# controller.net
KiCad netlist of a schematic drawn in EAGLE
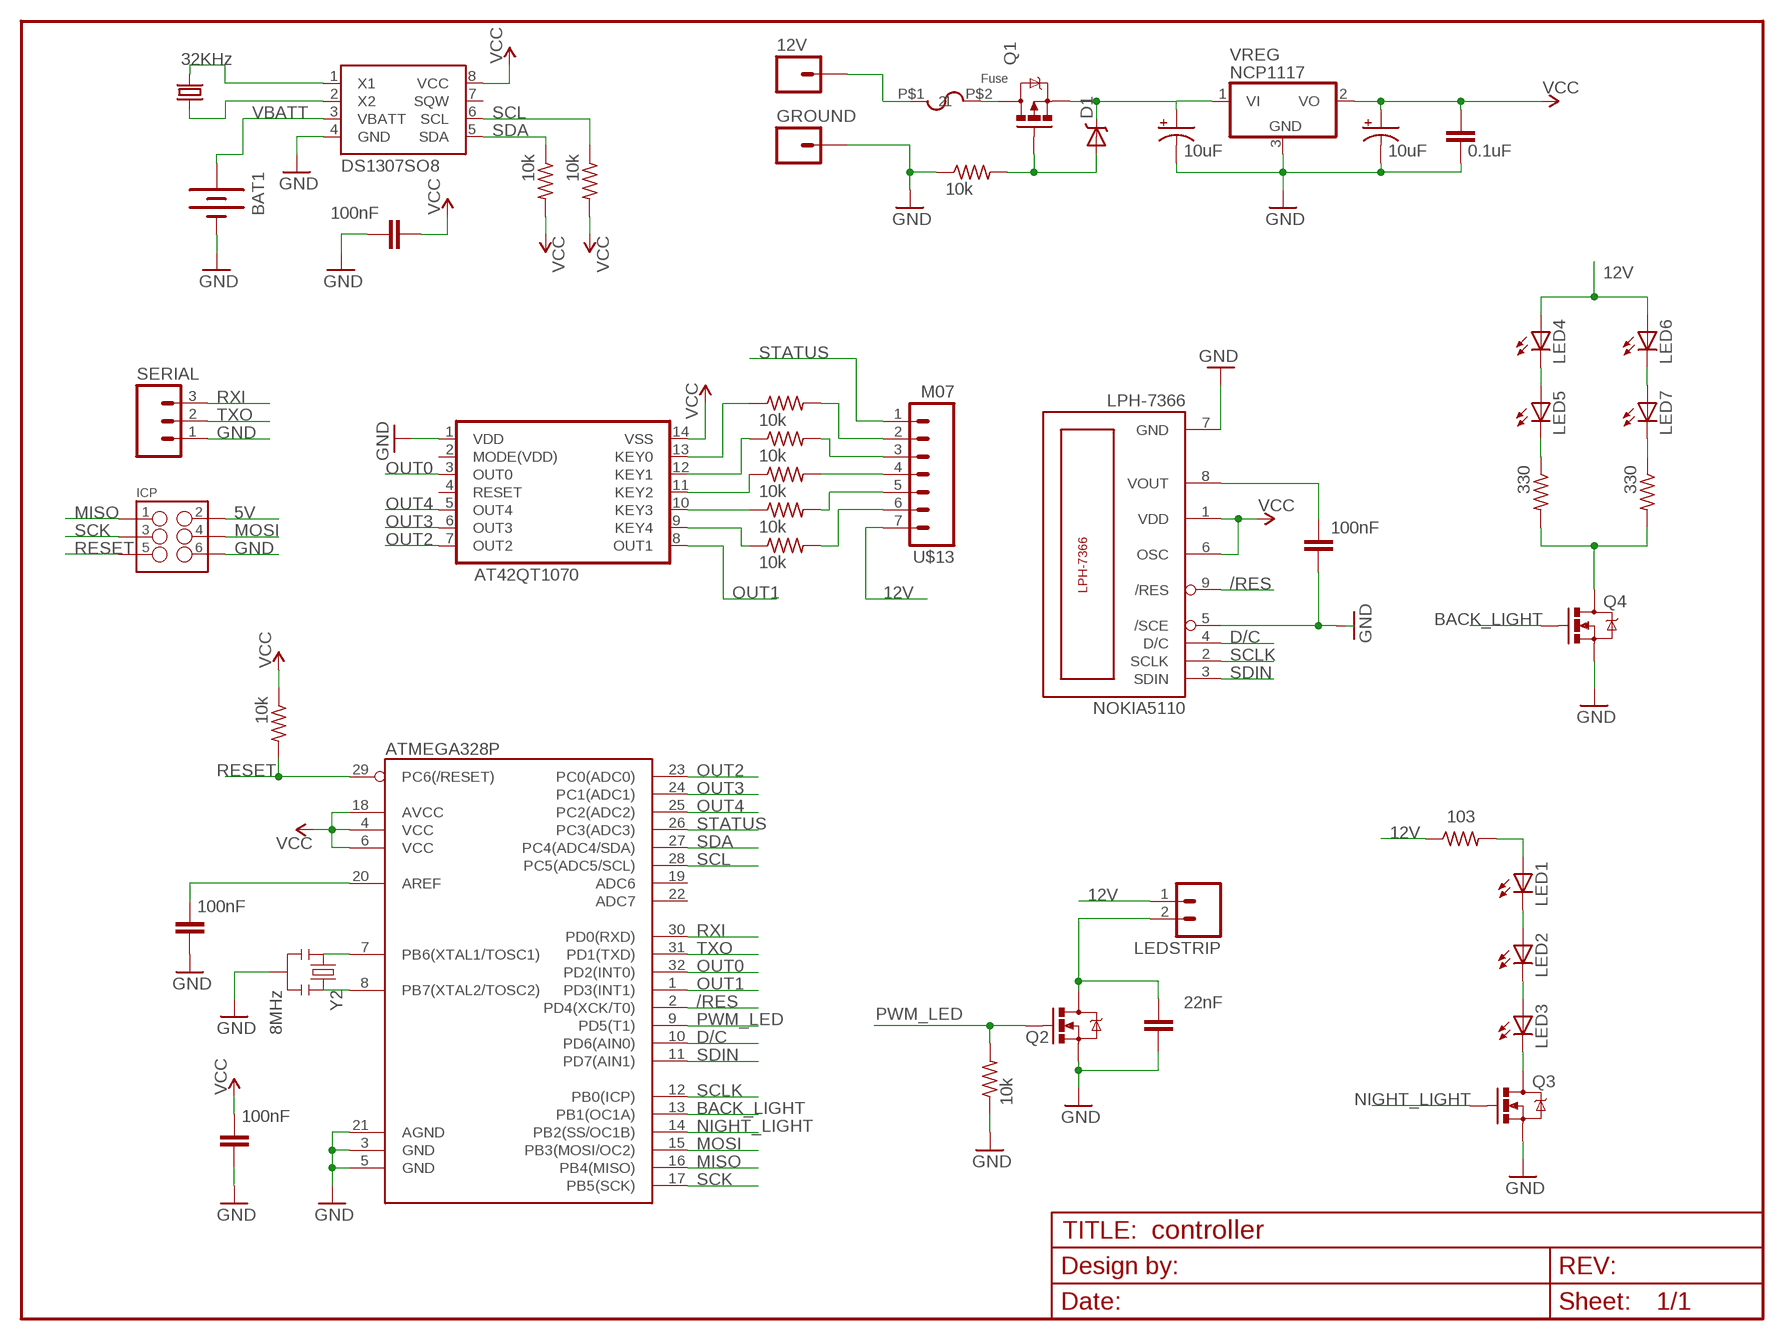
[diagram p0: schematic, sheet 1]

(export (version "E")
  (design (tool "Eeschema 10.0.6"))
  (components
    (comp (ref "12V")
      (value "M01PTH_LONGPAD")
      (footprint "eagle-import:1X01_LONGPAD")
      (libsource (lib "eagle-import") (part "M01PTH_LONGPAD"))
    )
    (comp (ref "AT42QT1070")
      (value "AT42QT1070")
      (footprint "eagle-import:SOIC-14")
      (libsource (lib "eagle-import") (part "AT42QT1070"))
    )
    (comp (ref "BAT1")
      (value "BATTERY12MM")
      (footprint "eagle-import:BATTCON_12MM")
      (libsource (lib "eagle-import") (part "BATTERY12MM"))
    )
    (comp (ref "C1")
      (value "100nF")
      (footprint "eagle-import:0805")
      (libsource (lib "eagle-import") (part "CAP0805"))
    )
    (comp (ref "C2")
      (value "100nF")
      (footprint "eagle-import:0805")
      (libsource (lib "eagle-import") (part "CAP0805"))
    )
    (comp (ref "C3")
      (value "100nF")
      (footprint "eagle-import:0805")
      (libsource (lib "eagle-import") (part "CAP0805"))
    )
    (comp (ref "C4")
      (value "22nF")
      (footprint "eagle-import:0805")
      (libsource (lib "eagle-import") (part "CAP0805"))
    )
    (comp (ref "C5")
      (value "10uF")
      (footprint "eagle-import:EIA3216-KIT")
      (libsource (lib "eagle-import") (part "CAP_POL1206-KIT"))
    )
    (comp (ref "C6")
      (value "100nF")
      (footprint "eagle-import:0805")
      (libsource (lib "eagle-import") (part "CAP0805"))
    )
    (comp (ref "C7")
      (value "10uF")
      (footprint "eagle-import:EIA3216-KIT")
      (libsource (lib "eagle-import") (part "CAP_POL1206-KIT"))
    )
    (comp (ref "C8")
      (value "0.1uF")
      (footprint "eagle-import:0805")
      (libsource (lib "eagle-import") (part "CAP0805"))
    )
    (comp (ref "D1")
      (value "DIODE-SCHOTTKYDO-214AA")
      (footprint "eagle-import:DO-214AA")
      (libsource (lib "eagle-import") (part "DIODE-SCHOTTKYDO-214AA"))
    )
    (comp (ref "GROUND")
      (value "M01PTH_LONGPAD")
      (footprint "eagle-import:1X01_LONGPAD")
      (libsource (lib "eagle-import") (part "M01PTH_LONGPAD"))
    )
    (comp (ref "ICP")
      (value "M03X2POGO_PINS")
      (footprint "eagle-import:2X3_POGO")
      (libsource (lib "eagle-import") (part "M03X2POGO_PINS"))
    )
    (comp (ref "LED1")
      (value "LED")
      (footprint "eagle-import:SIDEVIEW-LED")
      (libsource (lib "eagle-import") (part "LED"))
    )
    (comp (ref "LED2")
      (value "LED")
      (footprint "eagle-import:SIDEVIEW-LED")
      (libsource (lib "eagle-import") (part "LED"))
    )
    (comp (ref "LED3")
      (value "LED")
      (footprint "eagle-import:SIDEVIEW-LED")
      (libsource (lib "eagle-import") (part "LED"))
    )
    (comp (ref "LED4")
      (value "LED0603")
      (footprint "eagle-import:LED-0603")
      (libsource (lib "eagle-import") (part "LED0603"))
    )
    (comp (ref "LED5")
      (value "LED0603")
      (footprint "eagle-import:LED-0603")
      (libsource (lib "eagle-import") (part "LED0603"))
    )
    (comp (ref "LED6")
      (value "LED0603")
      (footprint "eagle-import:LED-0603")
      (libsource (lib "eagle-import") (part "LED0603"))
    )
    (comp (ref "LED7")
      (value "LED0603")
      (footprint "eagle-import:LED-0603")
      (libsource (lib "eagle-import") (part "LED0603"))
    )
    (comp (ref "LEDSTRIP")
      (value "M02LOCK_LONGPADS")
      (footprint "eagle-import:1X02_LOCK_LONGPADS")
      (libsource (lib "eagle-import") (part "M02LOCK_LONGPADS"))
    )
    (comp (ref "NOKIA5110")
      (value "LPH-7366")
      (footprint "eagle-import:NOKIA5110")
      (libsource (lib "eagle-import") (part "LPH-7366"))
    )
    (comp (ref "Q1")
      (value "MOSFET_PCHANNEL")
      (footprint "eagle-import:DPAK")
      (libsource (lib "eagle-import") (part "MOSFET_PCHANNEL"))
    )
    (comp (ref "Q2")
      (value "MOSFET-NCHANNELFDD8780")
      (footprint "eagle-import:DPAK@1")
      (libsource (lib "eagle-import") (part "MOSFET-NCHANNELFDD8780"))
    )
    (comp (ref "Q3")
      (value "MOSFET-NCHANNELBSS123LT1G")
      (footprint "eagle-import:SOT23")
      (libsource (lib "eagle-import") (part "MOSFET-NCHANNELBSS123LT1G"))
    )
    (comp (ref "Q4")
      (value "MOSFET-NCHANNELBSS123LT1G")
      (footprint "eagle-import:SOT23")
      (libsource (lib "eagle-import") (part "MOSFET-NCHANNELBSS123LT1G"))
    )
    (comp (ref "SERIAL")
      (value "M03POGO_PIN_HOLES_ONLY")
      (footprint "eagle-import:1X03_PP_HOLES_ONLY")
      (libsource (lib "eagle-import") (part "M03POGO_PIN_HOLES_ONLY"))
    )
    (comp (ref "U$1")
      (value "FRAME_LETTER")
      (footprint "eagle-import:CREATIVE_COMMONS")
      (libsource (lib "eagle-import") (part "FRAME_LETTER"))
    )
    (comp (ref "U$2")
      (value "10k")
      (footprint "eagle-import:RESISTOR-0805")
      (libsource (lib "eagle-import") (part "RESISTOR"))
    )
    (comp (ref "U$3")
      (value "DS1307SO8")
      (footprint "eagle-import:SO08")
      (libsource (lib "eagle-import") (part "DS1307SO8"))
    )
    (comp (ref "U$4")
      (value "10k")
      (footprint "eagle-import:RESISTOR-0805")
      (libsource (lib "eagle-import") (part "RESISTOR"))
    )
    (comp (ref "U$5")
      (value "10k")
      (footprint "eagle-import:RESISTOR-0805")
      (libsource (lib "eagle-import") (part "RESISTOR"))
    )
    (comp (ref "U$7")
      (value "10k")
      (footprint "eagle-import:RESISTOR-0805")
      (libsource (lib "eagle-import") (part "RESISTOR"))
    )
    (comp (ref "U$8")
      (value "10k")
      (footprint "eagle-import:RESISTOR-0805")
      (libsource (lib "eagle-import") (part "RESISTOR"))
    )
    (comp (ref "U$9")
      (value "10k")
      (footprint "eagle-import:RESISTOR-0805")
      (libsource (lib "eagle-import") (part "RESISTOR"))
    )
    (comp (ref "U$10")
      (value "10k")
      (footprint "eagle-import:RESISTOR-0805")
      (libsource (lib "eagle-import") (part "RESISTOR"))
    )
    (comp (ref "U$11")
      (value "10k")
      (footprint "eagle-import:RESISTOR-0805")
      (libsource (lib "eagle-import") (part "RESISTOR"))
    )
    (comp (ref "U$12")
      (value "Fuse")
      (footprint "eagle-import:FUSE-LITTLE-251")
      (libsource (lib "eagle-import") (part "FUSE"))
    )
    (comp (ref "U$13")
      (value "M07")
      (footprint "eagle-import:M07-SMD")
      (libsource (lib "eagle-import") (part "M07"))
    )
    (comp (ref "U$14")
      (value "10k")
      (footprint "eagle-import:RESISTOR-0805")
      (libsource (lib "eagle-import") (part "RESISTOR"))
    )
    (comp (ref "U$15")
      (value "10k")
      (footprint "eagle-import:RESISTOR-0805")
      (libsource (lib "eagle-import") (part "RESISTOR"))
    )
    (comp (ref "U$16")
      (value "103")
      (footprint "eagle-import:RESISTOR-0805")
      (libsource (lib "eagle-import") (part "RESISTOR"))
    )
    (comp (ref "U$17")
      (value "330")
      (footprint "eagle-import:RESISTOR-0805")
      (libsource (lib "eagle-import") (part "RESISTOR"))
    )
    (comp (ref "U$18")
      (value "330")
      (footprint "eagle-import:RESISTOR-0805")
      (libsource (lib "eagle-import") (part "RESISTOR"))
    )
    (comp (ref "U1")
      (value "ATMEGA328P")
      (footprint "eagle-import:TQFP32-08")
      (libsource (lib "eagle-import") (part "ATMEGA328_SMT"))
    )
    (comp (ref "VREG")
      (value "NCP1117")
      (footprint "eagle-import:TO252")
      (libsource (lib "eagle-import") (part "78DT05"))
    )
    (comp (ref "Y1")
      (value "32KHz")
      (footprint "eagle-import:CRYSTAL-32KHZ-SMD")
      (libsource (lib "eagle-import") (part "CRYSTAL32-SMD"))
    )
    (comp (ref "Y2")
      (value "8MHz")
      (footprint "eagle-import:RESONATOR-SMD")
      (libsource (lib "eagle-import") (part "RESONATOR16MHZ"))
    )
  )
  (nets
    (net (code "1") (name "/12V") (class "Default")
      (node (ref "C5") (pin "A") (pinfunction "+_A") (pintype "passive"))
      (node (ref "D1") (pin "C") (pinfunction "C_C") (pintype "passive"))
      (node (ref "LED4") (pin "A") (pinfunction "A_A") (pintype "passive"))
      (node (ref "LED6") (pin "A") (pinfunction "A_A") (pintype "passive"))
      (node (ref "LEDSTRIP") (pin "1") (pinfunction "1_1") (pintype "passive"))
      (node (ref "Q1") (pin "3") (pinfunction "S_3") (pintype "passive"))
      (node (ref "U$13") (pin "7") (pinfunction "7_7") (pintype "passive"))
      (node (ref "U$16") (pin "1") (pinfunction "1_1") (pintype "passive"))
      (node (ref "VREG") (pin "1") (pinfunction "VI_1") (pintype "input"))
    )
    (net (code "2") (name "/BACK_LIGHT") (class "Default")
      (node (ref "Q4") (pin "1") (pinfunction "G_1") (pintype "passive"))
      (node (ref "U1") (pin "13") (pinfunction "PB1(OC1A)_13") (pintype "bidirectional"))
    )
    (net (code "3") (name "/D{slash}C") (class "Default")
      (node (ref "NOKIA5110") (pin "4") (pinfunction "D/C_4") (pintype "input"))
      (node (ref "U1") (pin "10") (pinfunction "PD6(AIN0)_10") (pintype "bidirectional"))
    )
    (net (code "4") (name "/MISO") (class "Default")
      (node (ref "ICP") (pin "P$1") (pinfunction "1_P$1") (pintype "bidirectional"))
      (node (ref "U1") (pin "16") (pinfunction "PB4(MISO)_16") (pintype "bidirectional"))
    )
    (net (code "5") (name "/MOSI") (class "Default")
      (node (ref "ICP") (pin "P$4") (pinfunction "4_P$4") (pintype "bidirectional"))
      (node (ref "U1") (pin "15") (pinfunction "PB3(MOSI/OC2)_15") (pintype "bidirectional"))
    )
    (net (code "6") (name "/NIGHT_LIGHT") (class "Default")
      (node (ref "Q3") (pin "1") (pinfunction "G_1") (pintype "passive"))
      (node (ref "U1") (pin "14") (pinfunction "PB2(SS/OC1B)_14") (pintype "bidirectional"))
    )
    (net (code "7") (name "/OUT0") (class "Default")
      (node (ref "AT42QT1070") (pin "3") (pinfunction "OUT0_3") (pintype "bidirectional"))
      (node (ref "U1") (pin "32") (pinfunction "PD2(INT0)_32") (pintype "bidirectional"))
    )
    (net (code "8") (name "/OUT1") (class "Default")
      (node (ref "AT42QT1070") (pin "8") (pinfunction "OUT1_8") (pintype "bidirectional"))
      (node (ref "U1") (pin "1") (pinfunction "PD3(INT1)_1") (pintype "bidirectional"))
    )
    (net (code "9") (name "/OUT2") (class "Default")
      (node (ref "AT42QT1070") (pin "7") (pinfunction "OUT2_7") (pintype "bidirectional"))
      (node (ref "U1") (pin "23") (pinfunction "PC0(ADC0)_23") (pintype "bidirectional"))
    )
    (net (code "10") (name "/OUT3") (class "Default")
      (node (ref "AT42QT1070") (pin "6") (pinfunction "OUT3_6") (pintype "bidirectional"))
      (node (ref "U1") (pin "24") (pinfunction "PC1(ADC1)_24") (pintype "bidirectional"))
    )
    (net (code "11") (name "/OUT4") (class "Default")
      (node (ref "AT42QT1070") (pin "5") (pinfunction "OUT4_5") (pintype "bidirectional"))
      (node (ref "U1") (pin "25") (pinfunction "PC2(ADC2)_25") (pintype "bidirectional"))
    )
    (net (code "12") (name "/PWM_LED") (class "Default")
      (node (ref "Q2") (pin "1") (pinfunction "G_1") (pintype "passive"))
      (node (ref "U$15") (pin "2") (pinfunction "2_2") (pintype "passive"))
      (node (ref "U1") (pin "9") (pinfunction "PD5(T1)_9") (pintype "bidirectional"))
    )
    (net (code "13") (name "/RESET") (class "Default")
      (node (ref "ICP") (pin "P$5") (pinfunction "5_P$5") (pintype "bidirectional"))
      (node (ref "U$2") (pin "2") (pinfunction "2_2") (pintype "passive"))
      (node (ref "U1") (pin "29") (pinfunction "PC6(/RESET)_29") (pintype "bidirectional"))
    )
    (net (code "14") (name "/RXI") (class "Default")
      (node (ref "SERIAL") (pin "3") (pinfunction "3_3") (pintype "passive"))
      (node (ref "U1") (pin "30") (pinfunction "PD0(RXD)_30") (pintype "bidirectional"))
    )
    (net (code "15") (name "/SCK") (class "Default")
      (node (ref "ICP") (pin "P$3") (pinfunction "3_P$3") (pintype "bidirectional"))
      (node (ref "U1") (pin "17") (pinfunction "PB5(SCK)_17") (pintype "bidirectional"))
    )
    (net (code "16") (name "/SCL") (class "Default")
      (node (ref "U$3") (pin "6") (pinfunction "SCL_6") (pintype "bidirectional"))
      (node (ref "U$5") (pin "1") (pinfunction "1_1") (pintype "passive"))
      (node (ref "U1") (pin "28") (pinfunction "PC5(ADC5/SCL)_28") (pintype "bidirectional"))
    )
    (net (code "17") (name "/SCLK") (class "Default")
      (node (ref "NOKIA5110") (pin "2") (pinfunction "SCLK_2") (pintype "input"))
      (node (ref "U1") (pin "12") (pinfunction "PB0(ICP)_12") (pintype "bidirectional"))
    )
    (net (code "18") (name "/SDA") (class "Default")
      (node (ref "U$3") (pin "5") (pinfunction "SDA_5") (pintype "bidirectional"))
      (node (ref "U$4") (pin "1") (pinfunction "1_1") (pintype "passive"))
      (node (ref "U1") (pin "27") (pinfunction "PC4(ADC4/SDA)_27") (pintype "bidirectional"))
    )
    (net (code "19") (name "/SDIN") (class "Default")
      (node (ref "NOKIA5110") (pin "3") (pinfunction "SDIN_3") (pintype "input"))
      (node (ref "U1") (pin "11") (pinfunction "PD7(AIN1)_11") (pintype "bidirectional"))
    )
    (net (code "20") (name "/STATUS") (class "Default")
      (node (ref "U$13") (pin "1") (pinfunction "1_1") (pintype "passive"))
      (node (ref "U1") (pin "26") (pinfunction "PC3(ADC3)_26") (pintype "bidirectional"))
    )
    (net (code "21") (name "/TXO") (class "Default")
      (node (ref "SERIAL") (pin "2") (pinfunction "2_2") (pintype "passive"))
      (node (ref "U1") (pin "31") (pinfunction "PD1(TXD)_31") (pintype "bidirectional"))
    )
    (net (code "22") (name "/VBATT") (class "Default")
      (node (ref "BAT1") (pin "PWR@1") (pinfunction "+_PWR@1") (pintype "power_in"))
      (node (ref "U$3") (pin "3") (pinfunction "VBATT_3") (pintype "bidirectional"))
    )
    (net (code "23") (name "/{slash}RES") (class "Default")
      (node (ref "NOKIA5110") (pin "9") (pinfunction "/RES_9") (pintype "input"))
      (node (ref "U1") (pin "2") (pinfunction "PD4(XCK/T0)_2") (pintype "bidirectional"))
    )
    (net (code "24") (name "GND") (class "Default")
      (node (ref "AT42QT1070") (pin "1") (pinfunction "VDD_1") (pintype "power_in"))
      (node (ref "BAT1") (pin "GND") (pinfunction "-_GND") (pintype "power_in"))
      (node (ref "C1") (pin "2") (pinfunction "2_2") (pintype "passive"))
      (node (ref "C2") (pin "2") (pinfunction "2_2") (pintype "passive"))
      (node (ref "C3") (pin "2") (pinfunction "2_2") (pintype "passive"))
      (node (ref "C4") (pin "1") (pinfunction "1_1") (pintype "passive"))
      (node (ref "C5") (pin "C") (pinfunction "-_C") (pintype "passive"))
      (node (ref "C6") (pin "1") (pinfunction "1_1") (pintype "passive"))
      (node (ref "C7") (pin "C") (pinfunction "-_C") (pintype "passive"))
      (node (ref "C8") (pin "2") (pinfunction "2_2") (pintype "passive"))
      (node (ref "GROUND") (pin "1") (pinfunction "1_1") (pintype "passive"))
      (node (ref "ICP") (pin "P$6") (pinfunction "6_P$6") (pintype "bidirectional"))
      (node (ref "NOKIA5110") (pin "5") (pinfunction "/SCE_5") (pintype "input"))
      (node (ref "NOKIA5110") (pin "7") (pinfunction "GND_7") (pintype "power_in"))
      (node (ref "Q2") (pin "3") (pinfunction "S_3") (pintype "passive"))
      (node (ref "Q3") (pin "2") (pinfunction "S_2") (pintype "passive"))
      (node (ref "Q4") (pin "2") (pinfunction "S_2") (pintype "passive"))
      (node (ref "SERIAL") (pin "1") (pinfunction "1_1") (pintype "passive"))
      (node (ref "U$14") (pin "1") (pinfunction "1_1") (pintype "passive"))
      (node (ref "U$15") (pin "1") (pinfunction "1_1") (pintype "passive"))
      (node (ref "U$3") (pin "4") (pinfunction "GND_4") (pintype "bidirectional"))
      (node (ref "U1") (pin "21") (pinfunction "AGND_21") (pintype "bidirectional"))
      (node (ref "U1") (pin "3") (pinfunction "GND_3") (pintype "bidirectional"))
      (node (ref "U1") (pin "5") (pinfunction "GND_5") (pintype "bidirectional"))
      (node (ref "VREG") (pin "3") (pinfunction "GND_3") (pintype "passive"))
      (node (ref "Y2") (pin "2") (pinfunction "2_2") (pintype "passive"))
    )
    (net (code "25") (name "Net-(AT42QT1070-KEY0)") (class "Default")
      (node (ref "AT42QT1070") (pin "13") (pinfunction "KEY0_13") (pintype "bidirectional"))
      (node (ref "U$7") (pin "1") (pinfunction "1_1") (pintype "passive"))
    )
    (net (code "26") (name "Net-(AT42QT1070-KEY1)") (class "Default")
      (node (ref "AT42QT1070") (pin "12") (pinfunction "KEY1_12") (pintype "bidirectional"))
      (node (ref "U$8") (pin "1") (pinfunction "1_1") (pintype "passive"))
    )
    (net (code "27") (name "Net-(AT42QT1070-KEY2)") (class "Default")
      (node (ref "AT42QT1070") (pin "11") (pinfunction "KEY2_11") (pintype "bidirectional"))
      (node (ref "U$9") (pin "1") (pinfunction "1_1") (pintype "passive"))
    )
    (net (code "28") (name "Net-(AT42QT1070-KEY3)") (class "Default")
      (node (ref "AT42QT1070") (pin "10") (pinfunction "KEY3_10") (pintype "bidirectional"))
      (node (ref "U$10") (pin "1") (pinfunction "1_1") (pintype "passive"))
    )
    (net (code "29") (name "Net-(AT42QT1070-KEY4)") (class "Default")
      (node (ref "AT42QT1070") (pin "9") (pinfunction "KEY4_9") (pintype "bidirectional"))
      (node (ref "U$11") (pin "1") (pinfunction "1_1") (pintype "passive"))
    )
    (net (code "30") (name "Net-(LED1-A)") (class "Default")
      (node (ref "LED1") (pin "P$1") (pinfunction "A_P$1") (pintype "passive"))
      (node (ref "U$16") (pin "2") (pinfunction "2_2") (pintype "passive"))
    )
    (net (code "31") (name "Net-(LED1-C)") (class "Default")
      (node (ref "LED1") (pin "P$2") (pinfunction "C_P$2") (pintype "passive"))
      (node (ref "LED2") (pin "P$1") (pinfunction "A_P$1") (pintype "passive"))
    )
    (net (code "32") (name "Net-(LED2-C)") (class "Default")
      (node (ref "LED2") (pin "P$2") (pinfunction "C_P$2") (pintype "passive"))
      (node (ref "LED3") (pin "P$1") (pinfunction "A_P$1") (pintype "passive"))
    )
    (net (code "33") (name "Net-(LED3-C)") (class "Default")
      (node (ref "LED3") (pin "P$2") (pinfunction "C_P$2") (pintype "passive"))
      (node (ref "Q3") (pin "3") (pinfunction "D_3") (pintype "passive"))
    )
    (net (code "34") (name "Net-(LED4-PadC)") (class "Default")
      (node (ref "LED4") (pin "C") (pinfunction "C_C") (pintype "passive"))
      (node (ref "LED5") (pin "A") (pinfunction "A_A") (pintype "passive"))
    )
    (net (code "35") (name "Net-(LED5-PadC)") (class "Default")
      (node (ref "LED5") (pin "C") (pinfunction "C_C") (pintype "passive"))
      (node (ref "U$17") (pin "1") (pinfunction "1_1") (pintype "passive"))
    )
    (net (code "36") (name "Net-(LED6-PadC)") (class "Default")
      (node (ref "LED6") (pin "C") (pinfunction "C_C") (pintype "passive"))
      (node (ref "LED7") (pin "A") (pinfunction "A_A") (pintype "passive"))
    )
    (net (code "37") (name "Net-(LED7-PadC)") (class "Default")
      (node (ref "LED7") (pin "C") (pinfunction "C_C") (pintype "passive"))
      (node (ref "U$18") (pin "1") (pinfunction "1_1") (pintype "passive"))
    )
    (net (code "38") (name "Net-(NOKIA5110-VOUT)") (class "Default")
      (node (ref "C6") (pin "2") (pinfunction "2_2") (pintype "passive"))
      (node (ref "NOKIA5110") (pin "8") (pinfunction "VOUT_8") (pintype "passive"))
    )
    (net (code "39") (name "Net-(Q1-D)") (class "Default")
      (node (ref "Q1") (pin "4") (pinfunction "D_4") (pintype "passive"))
      (node (ref "U$12") (pin "P$2") (pinfunction "2_P$2") (pintype "bidirectional"))
    )
    (net (code "40") (name "Net-(Q1-G)") (class "Default")
      (node (ref "D1") (pin "A") (pinfunction "A_A") (pintype "passive"))
      (node (ref "Q1") (pin "1") (pinfunction "G_1") (pintype "passive"))
      (node (ref "U$14") (pin "2") (pinfunction "2_2") (pintype "passive"))
    )
    (net (code "41") (name "Net-(Q2-D)") (class "Default")
      (node (ref "C4") (pin "2") (pinfunction "2_2") (pintype "passive"))
      (node (ref "LEDSTRIP") (pin "2") (pinfunction "2_2") (pintype "passive"))
      (node (ref "Q2") (pin "4") (pinfunction "D_4") (pintype "passive"))
    )
    (net (code "42") (name "Net-(Q4-D)") (class "Default")
      (node (ref "Q4") (pin "3") (pinfunction "D_3") (pintype "passive"))
      (node (ref "U$17") (pin "2") (pinfunction "2_2") (pintype "passive"))
      (node (ref "U$18") (pin "2") (pinfunction "2_2") (pintype "passive"))
    )
    (net (code "43") (name "Net-(U$3-X1)") (class "Default")
      (node (ref "U$3") (pin "1") (pinfunction "X1_1") (pintype "bidirectional"))
      (node (ref "Y1") (pin "X2") (pinfunction "2_X2") (pintype "passive"))
    )
    (net (code "44") (name "Net-(U$3-X2)") (class "Default")
      (node (ref "U$3") (pin "2") (pinfunction "X2_2") (pintype "bidirectional"))
      (node (ref "Y1") (pin "X1") (pinfunction "1_X1") (pintype "passive"))
    )
    (net (code "45") (name "Net-(U$10-Pad2)") (class "Default")
      (node (ref "U$10") (pin "2") (pinfunction "2_2") (pintype "passive"))
      (node (ref "U$13") (pin "5") (pinfunction "5_5") (pintype "passive"))
    )
    (net (code "46") (name "Net-(U$11-Pad2)") (class "Default")
      (node (ref "U$11") (pin "2") (pinfunction "2_2") (pintype "passive"))
      (node (ref "U$13") (pin "6") (pinfunction "6_6") (pintype "passive"))
    )
    (net (code "47") (name "Net-(U$12-1)") (class "Default")
      (node (ref "12V") (pin "1") (pinfunction "1_1") (pintype "passive"))
      (node (ref "U$12") (pin "P$1") (pinfunction "1_P$1") (pintype "bidirectional"))
    )
    (net (code "48") (name "Net-(U$13-Pad2)") (class "Default")
      (node (ref "U$13") (pin "2") (pinfunction "2_2") (pintype "passive"))
      (node (ref "U$7") (pin "2") (pinfunction "2_2") (pintype "passive"))
    )
    (net (code "49") (name "Net-(U$13-Pad3)") (class "Default")
      (node (ref "U$13") (pin "3") (pinfunction "3_3") (pintype "passive"))
      (node (ref "U$8") (pin "2") (pinfunction "2_2") (pintype "passive"))
    )
    (net (code "50") (name "Net-(U$13-Pad4)") (class "Default")
      (node (ref "U$13") (pin "4") (pinfunction "4_4") (pintype "passive"))
      (node (ref "U$9") (pin "2") (pinfunction "2_2") (pintype "passive"))
    )
    (net (code "51") (name "Net-(U1-AREF)") (class "Default")
      (node (ref "C1") (pin "1") (pinfunction "1_1") (pintype "passive"))
      (node (ref "U1") (pin "20") (pinfunction "AREF_20") (pintype "bidirectional"))
    )
    (net (code "52") (name "Net-(U1-PB6(XTAL1{slash}TOSC1))") (class "Default")
      (node (ref "U1") (pin "7") (pinfunction "PB6(XTAL1/TOSC1)_7") (pintype "bidirectional"))
      (node (ref "Y2") (pin "1") (pinfunction "1_1") (pintype "passive"))
    )
    (net (code "53") (name "Net-(U1-PB7(XTAL2{slash}TOSC2))") (class "Default")
      (node (ref "U1") (pin "8") (pinfunction "PB7(XTAL2/TOSC2)_8") (pintype "bidirectional"))
      (node (ref "Y2") (pin "3") (pinfunction "3_3") (pintype "passive"))
    )
    (net (code "54") (name "VCC") (class "Default")
      (node (ref "AT42QT1070") (pin "14") (pinfunction "VSS_14") (pintype "power_in"))
      (node (ref "C2") (pin "1") (pinfunction "1_1") (pintype "passive"))
      (node (ref "C3") (pin "1") (pinfunction "1_1") (pintype "passive"))
      (node (ref "C7") (pin "A") (pinfunction "+_A") (pintype "passive"))
      (node (ref "C8") (pin "1") (pinfunction "1_1") (pintype "passive"))
      (node (ref "ICP") (pin "P$2") (pinfunction "2_P$2") (pintype "bidirectional"))
      (node (ref "NOKIA5110") (pin "1") (pinfunction "VDD_1") (pintype "power_in"))
      (node (ref "NOKIA5110") (pin "6") (pinfunction "OSC_6") (pintype "passive"))
      (node (ref "U$2") (pin "1") (pinfunction "1_1") (pintype "passive"))
      (node (ref "U$3") (pin "8") (pinfunction "VCC_8") (pintype "bidirectional"))
      (node (ref "U$4") (pin "2") (pinfunction "2_2") (pintype "passive"))
      (node (ref "U$5") (pin "2") (pinfunction "2_2") (pintype "passive"))
      (node (ref "U1") (pin "18") (pinfunction "AVCC_18") (pintype "bidirectional"))
      (node (ref "U1") (pin "4") (pinfunction "VCC_4") (pintype "bidirectional"))
      (node (ref "U1") (pin "6") (pinfunction "VCC_6") (pintype "bidirectional"))
      (node (ref "VREG") (pin "2") (pinfunction "VO_2") (pintype "passive"))
    )
    (net (code "55") (name "unconnected-(AT42QT1070-MODE(VDD)-Pad2)") (class "Default")
      (node (ref "AT42QT1070") (pin "2") (pinfunction "MODE(VDD)_2") (pintype "bidirectional"))
    )
    (net (code "56") (name "unconnected-(AT42QT1070-RESET-Pad4)") (class "Default")
      (node (ref "AT42QT1070") (pin "4") (pinfunction "RESET_4") (pintype "bidirectional"))
    )
    (net (code "57") (name "unconnected-(U$3-SQW-Pad7)") (class "Default")
      (node (ref "U$3") (pin "7") (pinfunction "SQW_7") (pintype "bidirectional"))
    )
    (net (code "58") (name "unconnected-(U1-ADC6-Pad19)") (class "Default")
      (node (ref "U1") (pin "19") (pinfunction "ADC6_19") (pintype "bidirectional"))
    )
    (net (code "59") (name "unconnected-(U1-ADC7-Pad22)") (class "Default")
      (node (ref "U1") (pin "22") (pinfunction "ADC7_22") (pintype "bidirectional"))
    )
  )
)
